# 0002_page_2.net
KiCad netlist of a schematic drawn in Altium Designer
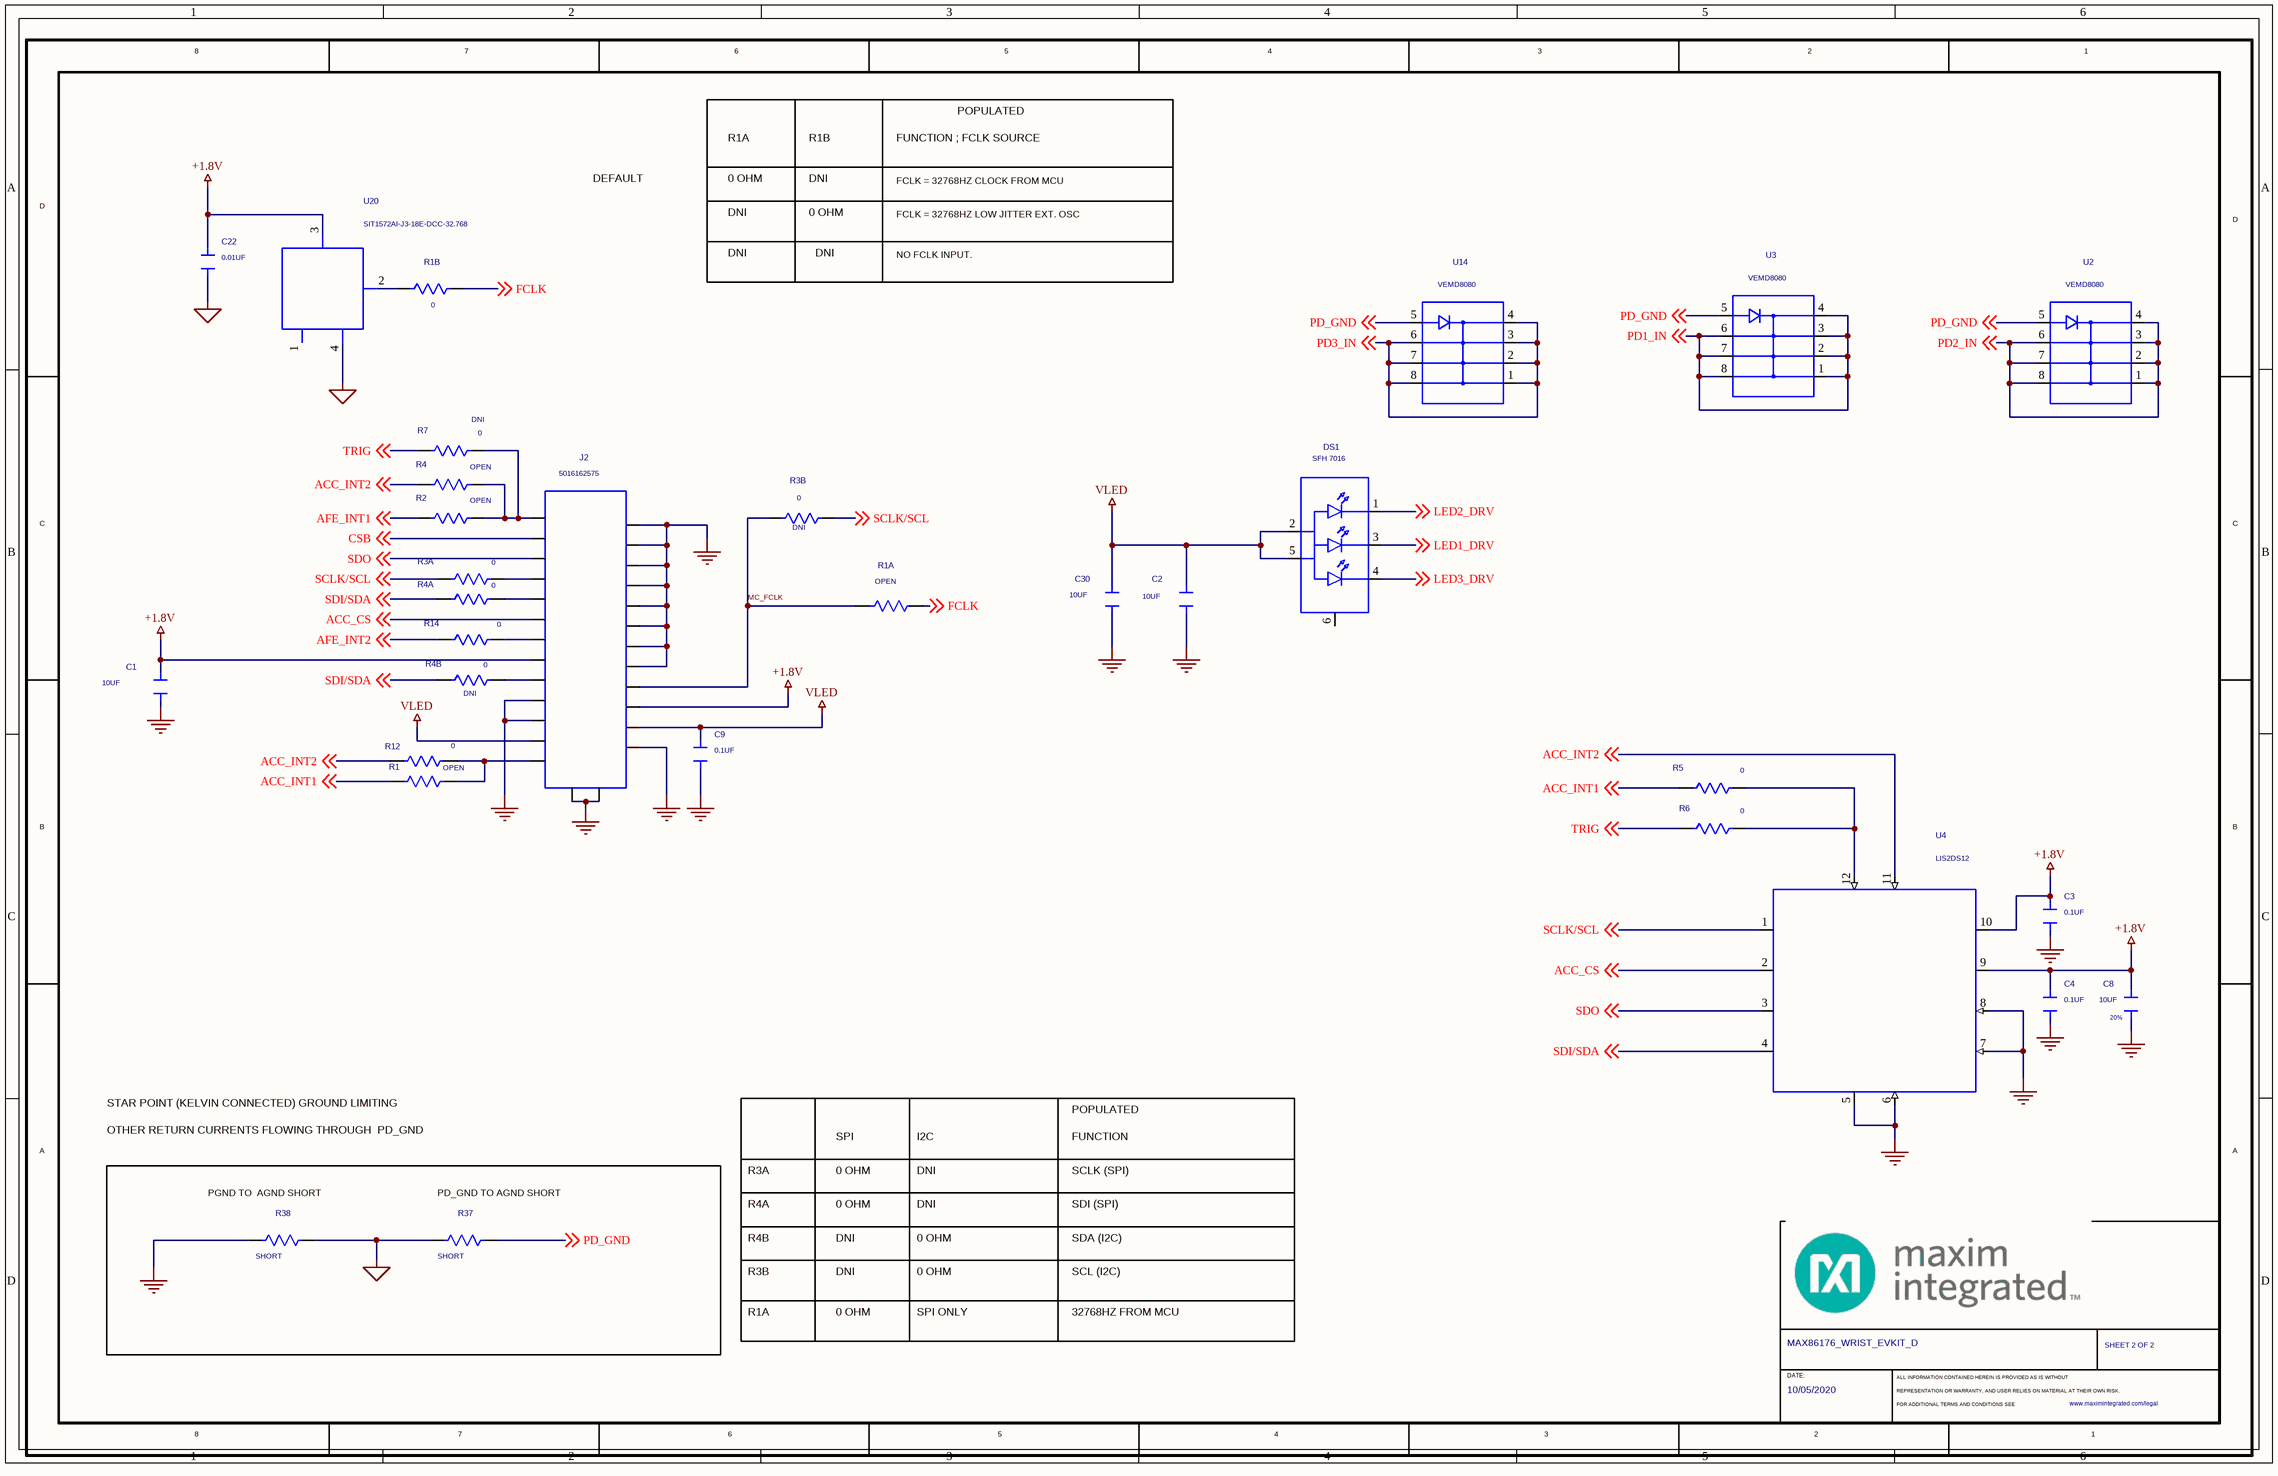
[diagram p0: 0002_page 2.SchDoc]

(export (version "E")
  (design (tool "Eeschema 10.0.6"))
  (components
    (comp (ref "C1")
      (value "10UF")
      (footprint "0603")
      (description "CAP; SMT (0603); 10UF; 20%; 25V; X5R; CERAMIC CHIP")
      (fields (field (name "MFG_PART_NUMBER") "GRM188R61E106MA73") (field (name "TOLERANCE") "20%"))
      (libsource (lib "*") (part "EK_CAP_NP"))
    )
    (comp (ref "C2")
      (value "10UF")
      (footprint "0603")
      (description "CAP; SMT (0603); 10UF; 20%; 25V; X5R; CERAMIC CHIP")
      (fields (field (name "MFG_PART_NUMBER") "GRM188R61E106MA73") (field (name "TOLERANCE") "20%"))
      (libsource (lib "*") (part "EK_CAP_NP"))
    )
    (comp (ref "C3")
      (value "0.1UF")
      (footprint "0603")
      (description "CAP; SMT (0603); 0.1UF; 10%; 100V; X7R; CERAMIC")
      (fields
        (field (name "MFG_PART_NUMBER") "GRM188R72A104KA35; CC0603KRX7R0BB104")
        (field (name "TOLERANCE") "10%")
      )
      (libsource (lib "*") (part "CAP_NP"))
    )
    (comp (ref "C4")
      (value "0.1UF")
      (footprint "0603")
      (description "CAP; SMT (0603); 0.1UF; 10%; 100V; X7R; CERAMIC")
      (fields
        (field (name "MFG_PART_NUMBER") "GRM188R72A104KA35; CC0603KRX7R0BB104")
        (field (name "TOLERANCE") "10%")
      )
      (libsource (lib "*") (part "CAP_NP"))
    )
    (comp (ref "C8")
      (value "10UF")
      (footprint "0402")
      (description "CAP; SMT (0402); 10UF; 20%; 10V; X5R; CERAMIC")
      (fields
        (field (name "MFG_PART_NUMBER") "GRM155R61A106ME44;GRM155R61A106ME11;0402ZD106MAT2A;CL05A106MP5NUNC")
        (field (name "TOLERANCE") "20%")
        (field (name "MANUFACTURER") "MURATA;MURATA;AVX;SAMSUNG")
      )
      (libsource (lib "*") (part "CAP_NP#1"))
    )
    (comp (ref "C9")
      (value "0.1UF")
      (footprint "CAPC0603X33M")
      (description "CAP; SMT (0201); 0.1UF; 10%; 10V; X5R; CERAMIC")
      (fields
        (field (name "MFG_PART_NUMBER") "GRM033R61A104KE15; LMK063BJ104KP")
        (field (name "MANUFACTURER") "MURATA;TAIYO YUDEN")
      )
      (libsource (lib "*") (part "CAP_NP"))
    )
    (comp (ref "C22")
      (value "0.01UF")
      (footprint "CAPC0603X33M")
      (description "CAP; SMT (0201); 0.01UF; 10%; 10V; X7R; CERAMIC")
      (fields
        (field (name "MFG_PART_NUMBER") "C0603X7R1A103K030BA;GRM033R71A103KA01;GCM033R71A103KA03;CGA1A2X7R1A103K030BA;0201ZC103KAT2A")
        (field (name "TOLERANCE") "10%")
      )
      (libsource (lib "*") (part "CAP_NP"))
    )
    (comp (ref "C30")
      (value "10UF")
      (footprint "0603")
      (description "CAP; SMT (0603); 10UF; 20%; 25V; X5R; CERAMIC CHIP")
      (fields (field (name "MFG_PART_NUMBER") "GRM188R61E106MA73") (field (name "TOLERANCE") "20%"))
      (libsource (lib "*") (part "EK_CAP_NP"))
    )
    (comp (ref "DS1")
      (value "SFH 7016")
      (footprint "LED_SFH7016")
      (fields (field (name "MANUFACTURER") "OSRAM"))
      (libsource (lib "*") (part "LED_6P"))
    )
    (comp (ref "J2")
      (value "5016162575")
      (footprint "MOLEX_501616-2575")
      (fields (field (name "MANUFACTURER") "MOLEX"))
      (libsource (lib "*") (part "501616-2575"))
    )
    (comp (ref "R1")
      (value "OPEN")
      (footprint "0402")
      (description "PACKAGE OUTLINE 0402 RESISTOR - EVKIT")
      (libsource (lib "*") (part "EVK_GENERIC_RESISTORS"))
    )
    (comp (ref "R1A")
      (value "OPEN")
      (footprint "RESC0603X33M")
      (description "PACKAGE OUTLINE 0201 RESISTOR - EVKIT")
      (libsource (lib "*") (part "EVK_GENERIC_RESISTORS#1"))
    )
    (comp (ref "R1B")
      (value "0")
      (footprint "RESC0603X33M")
      (description "RES; SMT (0201); 0; 1%; JUMPER; 0.0500W")
      (fields (field (name "MFG_PART_NUMBER") "CRCW02010000ZS;ERJ-1GN0R00") (field (name "TOLERANCE") "1%"))
      (libsource (lib "*") (part "RES_SMD#1"))
    )
    (comp (ref "R2")
      (value "OPEN")
      (footprint "0402")
      (description "PACKAGE OUTLINE 0402 RESISTOR - EVKIT")
      (libsource (lib "*") (part "EVK_GENERIC_RESISTORS"))
    )
    (comp (ref "R3A")
      (value "0")
      (footprint "0402")
      (description "RES; SMT (0402); 0; JUMPER; JUMPER; 0.1000W")
      (fields (field (name "MFG_PART_NUMBER") "ERJ-2GE0R00") (field (name "TOLERANCE") "0%"))
      (libsource (lib "*") (part "RES_SMD#1"))
    )
    (comp (ref "R3B")
      (value "0")
      (footprint "0402")
      (description "RES; SMT (0402); 0; JUMPER; JUMPER; 0.1000W")
      (fields
        (field (name "MFG_PART_NUMBER") "ERJ-2GE0R00")
        (field (name "TOLERANCE") "0%")
        (field (name "VARIANT") "DNI")
      )
      (libsource (lib "*") (part "RES_SMD#1"))
    )
    (comp (ref "R4")
      (value "OPEN")
      (footprint "0402")
      (description "PACKAGE OUTLINE 0402 RESISTOR - EVKIT")
      (libsource (lib "*") (part "EVK_GENERIC_RESISTORS"))
    )
    (comp (ref "R4A")
      (value "0")
      (footprint "0402")
      (description "RES; SMT (0402); 0; JUMPER; JUMPER; 0.1000W")
      (fields (field (name "MFG_PART_NUMBER") "ERJ-2GE0R00") (field (name "TOLERANCE") "0%"))
      (libsource (lib "*") (part "RES_SMD#1"))
    )
    (comp (ref "R4B")
      (value "0")
      (footprint "0402")
      (description "RES; SMT (0402); 0; JUMPER; JUMPER; 0.1000W")
      (fields
        (field (name "MFG_PART_NUMBER") "ERJ-2GE0R00")
        (field (name "TOLERANCE") "0%")
        (field (name "VARIANT") "DNI")
      )
      (libsource (lib "*") (part "RES_SMD#1"))
    )
    (comp (ref "R5")
      (value "0")
      (footprint "RESC0603X33M")
      (description "RES; SMT (0201); 0; 1%; JUMPER; 0.0500W")
      (fields (field (name "MFG_PART_NUMBER") "CRCW02010000ZS;ERJ-1GN0R00") (field (name "TOLERANCE") "1%"))
      (libsource (lib "*") (part "RES_SMD#1"))
    )
    (comp (ref "R6")
      (value "0")
      (footprint "RESC0603X33M")
      (description "RES; SMT (0201); 0; 1%; JUMPER; 0.0500W")
      (fields (field (name "MFG_PART_NUMBER") "CRCW02010000ZS;ERJ-1GN0R00") (field (name "TOLERANCE") "1%"))
      (libsource (lib "*") (part "RES_SMD#1"))
    )
    (comp (ref "R7")
      (value "0")
      (footprint "RESC0603X33M")
      (description "RES; SMT (0201); 0; 1%; JUMPER; 0.0500W")
      (fields
        (field (name "MFG_PART_NUMBER") "CRCW02010000ZS;ERJ-1GN0R00")
        (field (name "TOLERANCE") "1%")
        (field (name "VARIANT") "DNI")
      )
      (libsource (lib "*") (part "RES_SMD#1"))
    )
    (comp (ref "R12")
      (value "0")
      (footprint "RESC0603X33M")
      (description "RES; SMT (0201); 0; 1%; JUMPER; 0.0500W")
      (fields (field (name "MFG_PART_NUMBER") "CRCW02010000ZS;ERJ-1GN0R00") (field (name "TOLERANCE") "1%"))
      (libsource (lib "*") (part "RES_SMD#1"))
    )
    (comp (ref "R14")
      (value "0")
      (footprint "RESC0603X33M")
      (description "RES; SMT (0201); 0; 1%; JUMPER; 0.0500W")
      (fields (field (name "MFG_PART_NUMBER") "CRCW02010000ZS;ERJ-1GN0R00") (field (name "TOLERANCE") "1%"))
      (libsource (lib "*") (part "RES_SMD#1"))
    )
    (comp (ref "R37")
      (value "SHORT")
      (footprint "RESC0603X23L_SHORT")
      (description "PACKAGE OUTLINE 0201 RESISTOR - EVKIT FORM FACTOR FOOTRINT")
      (libsource (lib "*") (part "EVK_GENERIC_RESISTORS"))
    )
    (comp (ref "R38")
      (value "SHORT")
      (footprint "RESC0603X23L_SHORT")
      (description "PACKAGE OUTLINE 0201 RESISTOR - EVKIT FORM FACTOR FOOTRINT")
      (libsource (lib "*") (part "EVK_GENERIC_RESISTORS"))
    )
    (comp (ref "U2")
      (value "VEMD8080")
      (footprint "DIO_VEMD8080")
      (description "DIODE; PIN; SMT; VRM=20V; IF=0.05A ;NOTE:PURCHASE DIRECT FROM THE MANUFACTURER")
      (fields (field (name "MANUFACTURER") "VISHAY"))
      (libsource (lib "*") (part "DIO_PIN_8P"))
    )
    (comp (ref "U3")
      (value "VEMD8080")
      (footprint "DIO_VEMD8080")
      (description "DIODE; PIN; SMT; VRM=20V; IF=0.05A ;NOTE:PURCHASE DIRECT FROM THE MANUFACTURER")
      (fields (field (name "MANUFACTURER") "VISHAY"))
      (libsource (lib "*") (part "DIO_PIN_8P"))
    )
    (comp (ref "U4")
      (value "LIS2DS12")
      (footprint "STMC_LGA-12")
      (fields (field (name "MANUFACTURER") "ST MICROELECTRONICS"))
      (libsource (lib "*") (part "LIS2DS12"))
    )
    (comp (ref "U14")
      (value "VEMD8080")
      (footprint "DIO_VEMD8080")
      (description "DIODE; PIN; SMT; VRM=20V; IF=0.05A ;NOTE:PURCHASE DIRECT FROM THE MANUFACTURER")
      (fields (field (name "MANUFACTURER") "VISHAY"))
      (libsource (lib "*") (part "DIO_PIN_8P"))
    )
    (comp (ref "U20")
      (value "SIT1572AI-J3-18E-DCC-32.768")
      (footprint "OSC_SIT1572XX-JX-XXX")
      (description "OSCILLATOR; CSP 1.5 MM X 0.8 MM; 15PF; 32.768KHZ ; +/-10PPM")
      (fields (field (name "MANUFACTURER") "SITIME CORPORATION"))
      (libsource (lib "*") (part "SIT1572"))
    )
  )
  (nets
    (net (code "1") (name "+1.8V") (class "Default")
      (node (ref "C1") (pin "2") (pinfunction "2_2") (pintype "bidirectional"))
      (node (ref "C22") (pin "2") (pinfunction "2_2") (pintype "bidirectional"))
      (node (ref "C3") (pin "2") (pinfunction "2_2") (pintype "bidirectional"))
      (node (ref "C4") (pin "2") (pinfunction "2_2") (pintype "bidirectional"))
      (node (ref "C8") (pin "2") (pinfunction "2_2") (pintype "bidirectional"))
      (node (ref "J2") (pin "15") (pinfunction "15_15") (pintype "bidirectional"))
      (node (ref "J2") (pin "20") (pinfunction "20_20") (pintype "bidirectional"))
      (node (ref "U20") (pin "3") (pinfunction "VDD_3") (pintype "bidirectional"))
      (node (ref "U4") (pin "10") (pinfunction "VDDIO_10") (pintype "bidirectional"))
      (node (ref "U4") (pin "9") (pinfunction "VDD_9") (pintype "bidirectional"))
    )
    (net (code "2") (name "/MC_FCLK") (class "Default")
      (node (ref "J2") (pin "18") (pinfunction "18_18") (pintype "bidirectional"))
      (node (ref "R1A") (pin "1") (pinfunction "1_1") (pintype "bidirectional"))
      (node (ref "R3B") (pin "1") (pinfunction "1_1") (pintype "bidirectional"))
    )
    (net (code "3") (name "ACC_CS") (class "Default")
      (node (ref "J2") (pin "11") (pinfunction "11_11") (pintype "bidirectional"))
      (node (ref "U4") (pin "2") (pinfunction "CS_2") (pintype "bidirectional"))
    )
    (net (code "4") (name "ACC_INT1") (class "Default")
      (node (ref "R1") (pin "1") (pinfunction "1_1") (pintype "bidirectional"))
      (node (ref "R5") (pin "1") (pinfunction "1_1") (pintype "bidirectional"))
    )
    (net (code "5") (name "ACC_INT2") (class "Default")
      (node (ref "R12") (pin "1") (pinfunction "1_1") (pintype "bidirectional"))
      (node (ref "R4") (pin "1") (pinfunction "1_1") (pintype "bidirectional"))
      (node (ref "U4") (pin "11") (pinfunction "INT2_11") (pintype "input"))
    )
    (net (code "6") (name "AFE_INT1") (class "Default")
      (node (ref "R2") (pin "1") (pinfunction "1_1") (pintype "bidirectional"))
    )
    (net (code "7") (name "AFE_INT2") (class "Default")
      (node (ref "R14") (pin "1") (pinfunction "1_1") (pintype "bidirectional"))
    )
    (net (code "8") (name "AGND") (class "Default")
      (node (ref "C22") (pin "1") (pinfunction "1_1") (pintype "bidirectional"))
      (node (ref "R37") (pin "1") (pinfunction "1_1") (pintype "bidirectional"))
      (node (ref "R38") (pin "2") (pinfunction "2_2") (pintype "bidirectional"))
      (node (ref "U20") (pin "4") (pinfunction "GND_4") (pintype "input"))
    )
    (net (code "9") (name "CSB") (class "Default")
      (node (ref "J2") (pin "3") (pinfunction "3_3") (pintype "bidirectional"))
    )
    (net (code "10") (name "FCLK") (class "Default")
      (node (ref "R1A") (pin "2") (pinfunction "2_2") (pintype "bidirectional"))
      (node (ref "R1B") (pin "2") (pinfunction "2_2") (pintype "bidirectional"))
    )
    (net (code "11") (name "LED1_DRV") (class "Default")
      (node (ref "DS1") (pin "3") (pinfunction "K_2_3") (pintype "bidirectional"))
    )
    (net (code "12") (name "LED2_DRV") (class "Default")
      (node (ref "DS1") (pin "1") (pinfunction "K_1_1") (pintype "bidirectional"))
    )
    (net (code "13") (name "LED3_DRV") (class "Default")
      (node (ref "DS1") (pin "4") (pinfunction "K_3_4") (pintype "bidirectional"))
    )
    (net (code "14") (name "Net-(J2-Pad1)") (class "Default")
      (node (ref "J2") (pin "1") (pinfunction "1_1") (pintype "bidirectional"))
      (node (ref "R2") (pin "2") (pinfunction "2_2") (pintype "bidirectional"))
      (node (ref "R4") (pin "2") (pinfunction "2_2") (pintype "bidirectional"))
      (node (ref "R7") (pin "2") (pinfunction "2_2") (pintype "bidirectional"))
    )
    (net (code "15") (name "Net-(J2-Pad7)") (class "Default")
      (node (ref "J2") (pin "7") (pinfunction "7_7") (pintype "bidirectional"))
      (node (ref "R3A") (pin "2") (pinfunction "2_2") (pintype "bidirectional"))
    )
    (net (code "16") (name "Net-(J2-Pad9)") (class "Default")
      (node (ref "J2") (pin "9") (pinfunction "9_9") (pintype "bidirectional"))
      (node (ref "R4A") (pin "2") (pinfunction "2_2") (pintype "bidirectional"))
    )
    (net (code "17") (name "Net-(J2-Pad13)") (class "Default")
      (node (ref "J2") (pin "13") (pinfunction "13_13") (pintype "bidirectional"))
      (node (ref "R14") (pin "2") (pinfunction "2_2") (pintype "bidirectional"))
    )
    (net (code "18") (name "Net-(J2-Pad17)") (class "Default")
      (node (ref "J2") (pin "17") (pinfunction "17_17") (pintype "bidirectional"))
      (node (ref "R4B") (pin "2") (pinfunction "2_2") (pintype "bidirectional"))
    )
    (net (code "19") (name "Net-(J2-Pad25)") (class "Default")
      (node (ref "J2") (pin "25") (pinfunction "25_25") (pintype "bidirectional"))
      (node (ref "R1") (pin "2") (pinfunction "2_2") (pintype "bidirectional"))
      (node (ref "R12") (pin "2") (pinfunction "2_2") (pintype "bidirectional"))
    )
    (net (code "20") (name "Net-(U4-INT1)") (class "Default")
      (node (ref "R5") (pin "2") (pinfunction "2_2") (pintype "bidirectional"))
      (node (ref "R6") (pin "2") (pinfunction "2_2") (pintype "bidirectional"))
      (node (ref "U4") (pin "12") (pinfunction "INT1_12") (pintype "input"))
    )
    (net (code "21") (name "Net-(U20-CLK_OUT)") (class "Default")
      (node (ref "R1B") (pin "1") (pinfunction "1_1") (pintype "bidirectional"))
      (node (ref "U20") (pin "2") (pinfunction "CLK_OUT_2") (pintype "output"))
    )
    (net (code "22") (name "PD1_IN") (class "Default")
      (node (ref "U3") (pin "1") (pinfunction "K_1_1") (pintype "bidirectional"))
      (node (ref "U3") (pin "2") (pinfunction "K_2_2") (pintype "bidirectional"))
      (node (ref "U3") (pin "3") (pinfunction "K_3_3") (pintype "bidirectional"))
      (node (ref "U3") (pin "4") (pinfunction "K_4_4") (pintype "bidirectional"))
      (node (ref "U3") (pin "6") (pinfunction "K_5_6") (pintype "bidirectional"))
      (node (ref "U3") (pin "7") (pinfunction "K_6_7") (pintype "bidirectional"))
      (node (ref "U3") (pin "8") (pinfunction "K_7_8") (pintype "bidirectional"))
    )
    (net (code "23") (name "PD2_IN") (class "Default")
      (node (ref "U2") (pin "1") (pinfunction "K_1_1") (pintype "bidirectional"))
      (node (ref "U2") (pin "2") (pinfunction "K_2_2") (pintype "bidirectional"))
      (node (ref "U2") (pin "3") (pinfunction "K_3_3") (pintype "bidirectional"))
      (node (ref "U2") (pin "4") (pinfunction "K_4_4") (pintype "bidirectional"))
      (node (ref "U2") (pin "6") (pinfunction "K_5_6") (pintype "bidirectional"))
      (node (ref "U2") (pin "7") (pinfunction "K_6_7") (pintype "bidirectional"))
      (node (ref "U2") (pin "8") (pinfunction "K_7_8") (pintype "bidirectional"))
    )
    (net (code "24") (name "PD3_IN") (class "Default")
      (node (ref "U14") (pin "1") (pinfunction "K_1_1") (pintype "bidirectional"))
      (node (ref "U14") (pin "2") (pinfunction "K_2_2") (pintype "bidirectional"))
      (node (ref "U14") (pin "3") (pinfunction "K_3_3") (pintype "bidirectional"))
      (node (ref "U14") (pin "4") (pinfunction "K_4_4") (pintype "bidirectional"))
      (node (ref "U14") (pin "6") (pinfunction "K_5_6") (pintype "bidirectional"))
      (node (ref "U14") (pin "7") (pinfunction "K_6_7") (pintype "bidirectional"))
      (node (ref "U14") (pin "8") (pinfunction "K_7_8") (pintype "bidirectional"))
    )
    (net (code "25") (name "PD_GND") (class "Default")
      (node (ref "R37") (pin "2") (pinfunction "2_2") (pintype "bidirectional"))
      (node (ref "U14") (pin "5") (pinfunction "A_5") (pintype "bidirectional"))
      (node (ref "U2") (pin "5") (pinfunction "A_5") (pintype "bidirectional"))
      (node (ref "U3") (pin "5") (pinfunction "A_5") (pintype "bidirectional"))
    )
    (net (code "26") (name "PGND") (class "Default")
      (node (ref "C1") (pin "1") (pinfunction "1_1") (pintype "bidirectional"))
      (node (ref "C2") (pin "1") (pinfunction "1_1") (pintype "bidirectional"))
      (node (ref "C3") (pin "1") (pinfunction "1_1") (pintype "bidirectional"))
      (node (ref "C30") (pin "1") (pinfunction "1_1") (pintype "bidirectional"))
      (node (ref "C4") (pin "1") (pinfunction "1_1") (pintype "bidirectional"))
      (node (ref "C8") (pin "1") (pinfunction "1_1") (pintype "bidirectional"))
      (node (ref "C9") (pin "1") (pinfunction "1_1") (pintype "bidirectional"))
      (node (ref "J2") (pin "10") (pinfunction "10_10") (pintype "bidirectional"))
      (node (ref "J2") (pin "12") (pinfunction "12_12") (pintype "bidirectional"))
      (node (ref "J2") (pin "14") (pinfunction "14_14") (pintype "bidirectional"))
      (node (ref "J2") (pin "16") (pinfunction "16_16") (pintype "bidirectional"))
      (node (ref "J2") (pin "19") (pinfunction "19_19") (pintype "bidirectional"))
      (node (ref "J2") (pin "2") (pinfunction "2_2") (pintype "bidirectional"))
      (node (ref "J2") (pin "21") (pinfunction "21_21") (pintype "bidirectional"))
      (node (ref "J2") (pin "24") (pinfunction "24_24") (pintype "bidirectional"))
      (node (ref "J2") (pin "26") (pinfunction "26_26") (pintype "bidirectional"))
      (node (ref "J2") (pin "27") (pinfunction "27_27") (pintype "bidirectional"))
      (node (ref "J2") (pin "4") (pinfunction "4_4") (pintype "bidirectional"))
      (node (ref "J2") (pin "6") (pinfunction "6_6") (pintype "bidirectional"))
      (node (ref "J2") (pin "8") (pinfunction "8_8") (pintype "bidirectional"))
      (node (ref "R38") (pin "1") (pinfunction "1_1") (pintype "bidirectional"))
      (node (ref "U4") (pin "5") (pinfunction "NC_5") (pintype "bidirectional"))
      (node (ref "U4") (pin "6") (pinfunction "GND_1_6") (pintype "input"))
      (node (ref "U4") (pin "7") (pinfunction "RES_7") (pintype "input"))
      (node (ref "U4") (pin "8") (pinfunction "GND_2_8") (pintype "input"))
    )
    (net (code "27") (name "SCLK{slash}SCL") (class "Default")
      (node (ref "R3A") (pin "1") (pinfunction "1_1") (pintype "bidirectional"))
      (node (ref "R3B") (pin "2") (pinfunction "2_2") (pintype "bidirectional"))
      (node (ref "U4") (pin "1") (pinfunction "SCL/SPC_1") (pintype "bidirectional"))
    )
    (net (code "28") (name "SDI{slash}SDA") (class "Default")
      (node (ref "R4A") (pin "1") (pinfunction "1_1") (pintype "bidirectional"))
      (node (ref "R4B") (pin "1") (pinfunction "1_1") (pintype "bidirectional"))
      (node (ref "U4") (pin "4") (pinfunction "SDA/SDI/SDO_4") (pintype "bidirectional"))
    )
    (net (code "29") (name "SDO") (class "Default")
      (node (ref "J2") (pin "5") (pinfunction "5_5") (pintype "bidirectional"))
      (node (ref "U4") (pin "3") (pinfunction "SDO/SA0_3") (pintype "bidirectional"))
    )
    (net (code "30") (name "TRIG") (class "Default")
      (node (ref "R6") (pin "1") (pinfunction "1_1") (pintype "bidirectional"))
      (node (ref "R7") (pin "1") (pinfunction "1_1") (pintype "bidirectional"))
    )
    (net (code "31") (name "VLED") (class "Default")
      (node (ref "C2") (pin "2") (pinfunction "2_2") (pintype "bidirectional"))
      (node (ref "C30") (pin "2") (pinfunction "2_2") (pintype "bidirectional"))
      (node (ref "C9") (pin "2") (pinfunction "2_2") (pintype "bidirectional"))
      (node (ref "DS1") (pin "2") (pinfunction "A_1_2") (pintype "bidirectional"))
      (node (ref "DS1") (pin "5") (pinfunction "A_2_5") (pintype "bidirectional"))
      (node (ref "J2") (pin "22") (pinfunction "22_22") (pintype "bidirectional"))
      (node (ref "J2") (pin "23") (pinfunction "23_23") (pintype "bidirectional"))
    )
    (net (code "32") (name "unconnected-(DS1-NC-Pad6)") (class "Default")
      (node (ref "DS1") (pin "6") (pinfunction "NC_6") (pintype "bidirectional"))
    )
    (net (code "33") (name "unconnected-(U20-NC-Pad1)") (class "Default")
      (node (ref "U20") (pin "1") (pinfunction "NC_1") (pintype "bidirectional"))
    )
  )
)
